# Tilt-MCU.net
KiCad netlist of a schematic drawn in Altium Designer
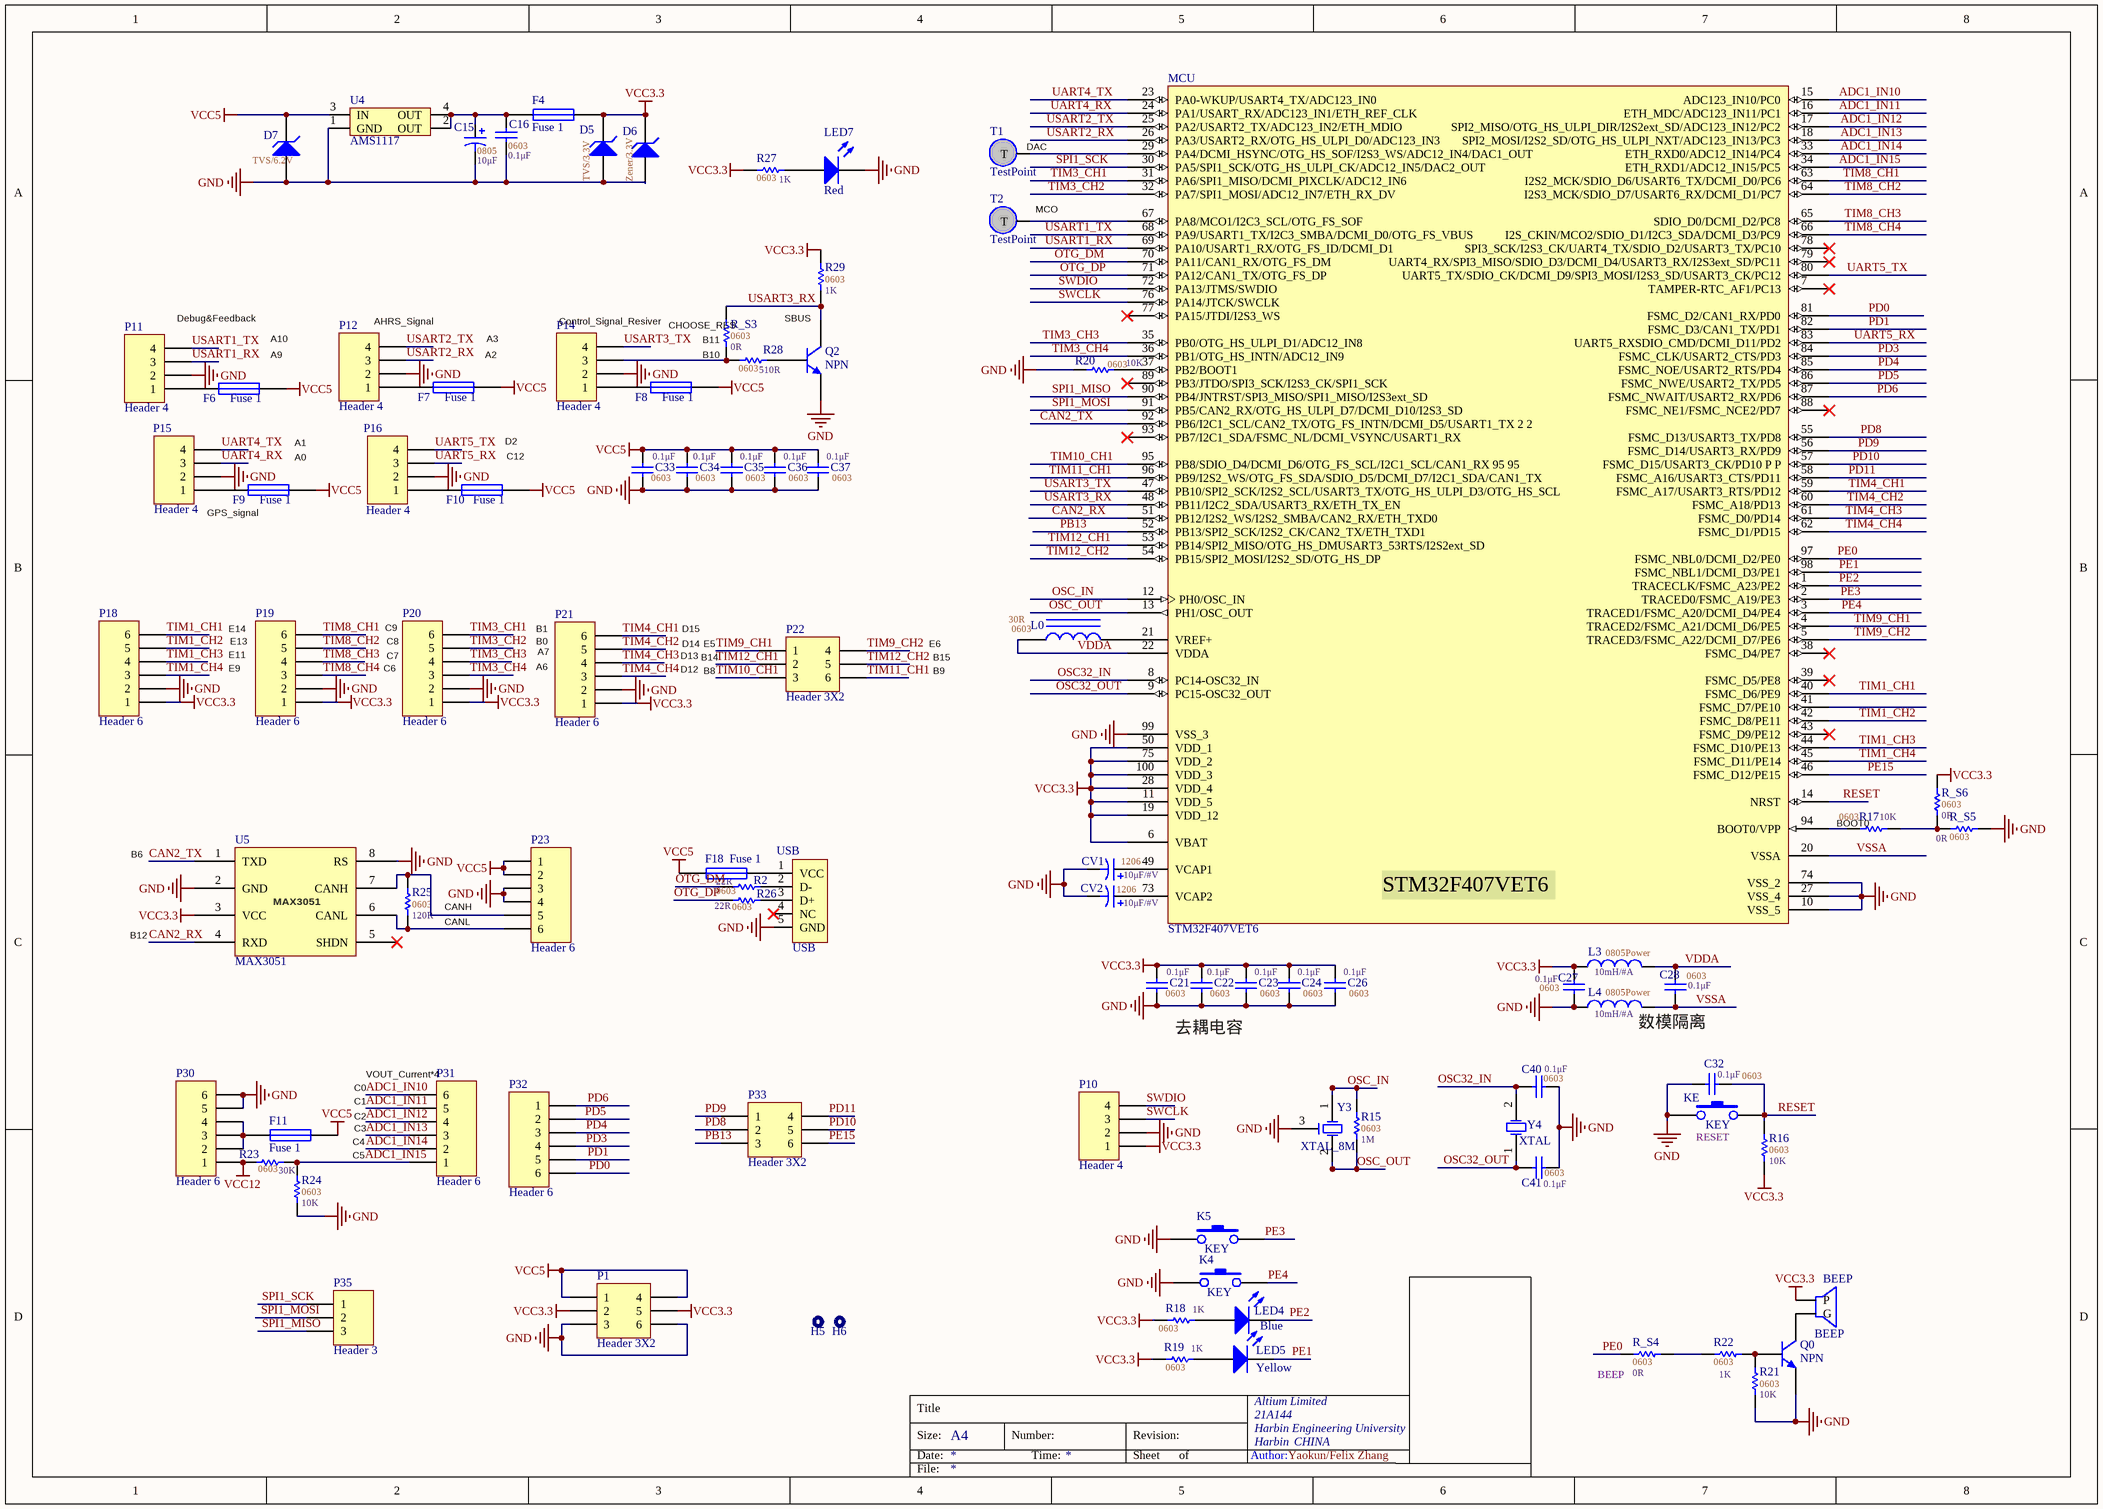
[diagram p0: Tilt-MCU.SchDoc]

(export (version "E")
  (design (tool "Eeschema 10.0.6"))
  (components
    (comp (ref "BEEP")
      (value "BEEP")
      (footprint "BELL-5")
      (libsource (lib "Belong_to_Kongkong") (part "BEEP"))
    )
    (comp (ref "C15")
      (value "10μF")
      (footprint "CAP_0805_20*12")
      (description "Polarized Capacitor (Axial)")
      (fields
        (field (name "PACKAGEREFERENCE") "0805")
        (field (name "Comment") "Polar")
        (field (name "PUBLISHER") "Altium Limited")
      )
      (libsource (lib "Belong_to_Kongkong") (part "Cap Pol"))
    )
    (comp (ref "C16")
      (value "0.1μF")
      (footprint "CAP_0603_16*08")
      (description "Capacitor")
      (fields
        (field (name "PACKAGEREFERENCE") "0603")
        (field (name "Comment") "0603")
        (field (name "PUBLISHER") "Altium Limited")
      )
      (libsource (lib "Belong_to_Kongkong") (part "Cap"))
    )
    (comp (ref "C21")
      (value "0.1μF")
      (footprint "CAP_0603_16*08")
      (description "Capacitor")
      (fields
        (field (name "PACKAGEREFERENCE") "0603")
        (field (name "Comment") "0603")
        (field (name "PUBLISHER") "Altium Limited")
      )
      (libsource (lib "Belong_to_Kongkong") (part "Cap"))
    )
    (comp (ref "C22")
      (value "0.1μF")
      (footprint "CAP_0603_16*08")
      (description "Capacitor")
      (fields
        (field (name "PACKAGEREFERENCE") "0603")
        (field (name "Comment") "0603")
        (field (name "PUBLISHER") "Altium Limited")
      )
      (libsource (lib "Belong_to_Kongkong") (part "Cap"))
    )
    (comp (ref "C23")
      (value "0.1μF")
      (footprint "CAP_0603_16*08")
      (description "Capacitor")
      (fields
        (field (name "PACKAGEREFERENCE") "0603")
        (field (name "Comment") "0603")
        (field (name "PUBLISHER") "Altium Limited")
      )
      (libsource (lib "Belong_to_Kongkong") (part "Cap"))
    )
    (comp (ref "C24")
      (value "0.1μF")
      (footprint "CAP_0603_16*08")
      (description "Capacitor")
      (fields
        (field (name "PACKAGEREFERENCE") "0603")
        (field (name "Comment") "0603")
        (field (name "PUBLISHER") "Altium Limited")
      )
      (libsource (lib "Belong_to_Kongkong") (part "Cap"))
    )
    (comp (ref "C26")
      (value "0.1μF")
      (footprint "CAP_0603_16*08")
      (description "Capacitor")
      (fields
        (field (name "PACKAGEREFERENCE") "0603")
        (field (name "Comment") "0603")
        (field (name "PUBLISHER") "Altium Limited")
      )
      (libsource (lib "Belong_to_Kongkong") (part "Cap"))
    )
    (comp (ref "C27")
      (value "0.1μF")
      (footprint "CAP_0603_16*08")
      (description "Capacitor")
      (fields
        (field (name "PACKAGEREFERENCE") "0603")
        (field (name "Comment") "0603")
        (field (name "PUBLISHER") "Altium Limited")
      )
      (libsource (lib "Belong_to_Kongkong") (part "Cap"))
    )
    (comp (ref "C28")
      (value "0.1μF")
      (footprint "CAP_0603_16*08")
      (description "Capacitor")
      (fields
        (field (name "PACKAGEREFERENCE") "0603")
        (field (name "Comment") "0603")
        (field (name "PUBLISHER") "Altium Limited")
      )
      (libsource (lib "Belong_to_Kongkong") (part "Cap"))
    )
    (comp (ref "C32")
      (value "0.1μF")
      (footprint "CAP_0603_16*08")
      (description "Capacitor")
      (fields
        (field (name "PACKAGEREFERENCE") "0603")
        (field (name "Comment") "0603")
        (field (name "PUBLISHER") "Altium Limited")
      )
      (libsource (lib "Belong_to_Kongkong") (part "Cap"))
    )
    (comp (ref "C33")
      (value "0.1μF")
      (footprint "CAP_0603_16*08")
      (description "Capacitor")
      (fields
        (field (name "PACKAGEREFERENCE") "0603")
        (field (name "Comment") "0603")
        (field (name "PUBLISHER") "Altium Limited")
      )
      (libsource (lib "Belong_to_Kongkong") (part "Cap"))
    )
    (comp (ref "C34")
      (value "0.1μF")
      (footprint "CAP_0603_16*08")
      (description "Capacitor")
      (fields
        (field (name "PACKAGEREFERENCE") "0603")
        (field (name "Comment") "0603")
        (field (name "PUBLISHER") "Altium Limited")
      )
      (libsource (lib "Belong_to_Kongkong") (part "Cap"))
    )
    (comp (ref "C35")
      (value "0.1μF")
      (footprint "CAP_0603_16*08")
      (description "Capacitor")
      (fields
        (field (name "PACKAGEREFERENCE") "0603")
        (field (name "Comment") "0603")
        (field (name "PUBLISHER") "Altium Limited")
      )
      (libsource (lib "Belong_to_Kongkong") (part "Cap"))
    )
    (comp (ref "C36")
      (value "0.1μF")
      (footprint "CAP_0603_16*08")
      (description "Capacitor")
      (fields
        (field (name "PACKAGEREFERENCE") "0603")
        (field (name "Comment") "0603")
        (field (name "PUBLISHER") "Altium Limited")
      )
      (libsource (lib "Belong_to_Kongkong") (part "Cap"))
    )
    (comp (ref "C37")
      (value "0.1μF")
      (footprint "CAP_0603_16*08")
      (description "Capacitor")
      (fields
        (field (name "PACKAGEREFERENCE") "0603")
        (field (name "Comment") "0603")
        (field (name "PUBLISHER") "Altium Limited")
      )
      (libsource (lib "Belong_to_Kongkong") (part "Cap"))
    )
    (comp (ref "C40")
      (value "0.1μF")
      (footprint "CAP_0603_16*08")
      (description "Capacitor")
      (fields
        (field (name "PACKAGEREFERENCE") "0603")
        (field (name "Comment") "0603")
        (field (name "PUBLISHER") "Altium Limited")
      )
      (libsource (lib "Belong_to_Kongkong") (part "Cap"))
    )
    (comp (ref "C41")
      (value "0.1μF")
      (footprint "CAP_0603_16*08")
      (description "Capacitor")
      (fields
        (field (name "PACKAGEREFERENCE") "0603")
        (field (name "Comment") "0603")
        (field (name "PUBLISHER") "Altium Limited")
      )
      (libsource (lib "Belong_to_Kongkong") (part "Cap"))
    )
    (comp (ref "CV1")
      (value "10μF/#V")
      (footprint "CAP_0805_20*12")
      (description "Polarized Capacitor (Axial)")
      (fields
        (field (name "PACKAGEREFERENCE") "1206")
        (field (name "Comment") "Polar")
        (field (name "PUBLISHER") "Altium Limited")
      )
      (libsource (lib "Belong_to_Kongkong") (part "Cap Pol"))
    )
    (comp (ref "CV2")
      (value "10μF/#V")
      (footprint "CAP_0805_20*12")
      (description "Polarized Capacitor (Axial)")
      (fields
        (field (name "PACKAGEREFERENCE") "1206")
        (field (name "Comment") "Polar")
        (field (name "PUBLISHER") "Altium Limited")
      )
      (libsource (lib "Belong_to_Kongkong") (part "Cap Pol"))
    )
    (comp (ref "D5")
      (value "TVS/3.3V")
      (footprint "SOD523")
      (description "Zener Diode")
      (fields (field (name "PUBLISHER") "Altium Limited"))
      (libsource (lib "Belong_to_Kongkong") (part "D Zener"))
    )
    (comp (ref "D6")
      (value "Zener/3.3V")
      (footprint "SOD323")
      (description "Zener Diode")
      (fields (field (name "PUBLISHER") "Altium Limited"))
      (libsource (lib "Belong_to_Kongkong") (part "D Zener"))
    )
    (comp (ref "D7")
      (value "TVS/6.2V")
      (footprint "SOD523")
      (description "Zener Diode")
      (fields (field (name "PUBLISHER") "Altium Limited"))
      (libsource (lib "Belong_to_Kongkong") (part "D Zener"))
    )
    (comp (ref "F4")
      (value "Fuse 1")
      (footprint "RES_0805_20*12")
      (description "Fuse")
      (fields (field (name "PUBLISHER") "Altium Limited"))
      (libsource (lib "Belong_to_Kongkong") (part "Fuse 1"))
    )
    (comp (ref "F6")
      (value "Fuse 1")
      (footprint "RES_0805_20*12")
      (description "Fuse")
      (fields (field (name "PUBLISHER") "Altium Limited"))
      (libsource (lib "Belong_to_Kongkong") (part "Fuse 1"))
    )
    (comp (ref "F7")
      (value "Fuse 1")
      (footprint "RES_0805_20*12")
      (description "Fuse")
      (fields (field (name "PUBLISHER") "Altium Limited"))
      (libsource (lib "Belong_to_Kongkong") (part "Fuse 1"))
    )
    (comp (ref "F8")
      (value "Fuse 1")
      (footprint "RES_0805_20*12")
      (description "Fuse")
      (fields (field (name "PUBLISHER") "Altium Limited"))
      (libsource (lib "Belong_to_Kongkong") (part "Fuse 1"))
    )
    (comp (ref "F9")
      (value "Fuse 1")
      (footprint "RES_0805_20*12")
      (description "Fuse")
      (fields (field (name "PUBLISHER") "Altium Limited"))
      (libsource (lib "Belong_to_Kongkong") (part "Fuse 1"))
    )
    (comp (ref "F10")
      (value "Fuse 1")
      (footprint "RES_0805_20*12")
      (description "Fuse")
      (fields (field (name "PUBLISHER") "Altium Limited"))
      (libsource (lib "Belong_to_Kongkong") (part "Fuse 1"))
    )
    (comp (ref "F11")
      (value "Fuse 1")
      (footprint "FUSE3.5*5.5")
      (description "Fuse")
      (fields (field (name "PUBLISHER") "Altium Limited"))
      (libsource (lib "Belong_to_Kongkong") (part "Fuse 1"))
    )
    (comp (ref "F18")
      (value "Fuse 1")
      (footprint "RES_0805_20*12")
      (description "Fuse")
      (fields (field (name "PUBLISHER") "Altium Limited"))
      (libsource (lib "Belong_to_Kongkong") (part "Fuse 1"))
    )
    (comp (ref "H5") (value "pad") (footprint "PAD_M2") (libsource (lib "Belong_to_Kongkong") (part "pad")))
    (comp (ref "H6") (value "pad") (footprint "PAD_M2") (libsource (lib "Belong_to_Kongkong") (part "pad")))
    (comp (ref "K4") (value "KEY") (footprint "KEY_2") (libsource (lib "Belong_to_Kongkong") (part "KEY")))
    (comp (ref "K5") (value "KEY") (footprint "KEY_2") (libsource (lib "Belong_to_Kongkong") (part "KEY")))
    (comp (ref "KE")
      (value "KEY")
      (footprint "KEY_2")
      (fields (field (name "ALTIUM_UNNAMED_1") "RESET"))
      (libsource (lib "Belong_to_Kongkong") (part "KEY"))
    )
    (comp (ref "L0")
      (value "30R")
      (footprint "IND_0603_16*08")
      (description "Magnetic-Core Inductor")
      (fields
        (field (name "PACKAGEDESCRIPTION") "0603")
        (field (name "Comment") "Inductor Iron")
        (field (name "PUBLISHER") "Altium Limited")
      )
      (libsource (lib "Belong_to_Kongkong") (part "Inductor Iron"))
    )
    (comp (ref "L3")
      (value "10mH/#A")
      (footprint "IND_0603_16*08")
      (description "Inductor")
      (fields
        (field (name "PACKAGEREFERENCE") "0805")
        (field (name "PACKAGEDESCRIPTION") "Power")
        (field (name "Comment") "MODEL?")
        (field (name "PUBLISHER") "Altium Limited")
      )
      (libsource (lib "Belong_to_Kongkong") (part "Inductor"))
    )
    (comp (ref "L4")
      (value "10mH/#A")
      (footprint "IND_0603_16*08")
      (description "Inductor")
      (fields
        (field (name "PACKAGEREFERENCE") "0805")
        (field (name "PACKAGEDESCRIPTION") "Power")
        (field (name "Comment") "MODEL?")
        (field (name "PUBLISHER") "Altium Limited")
      )
      (libsource (lib "Belong_to_Kongkong") (part "Inductor"))
    )
    (comp (ref "LED4")
      (value "Blue")
      (footprint "LED0603")
      (description "Typical RED, GREEN, YELLOW, AMBER GaAs LED")
      (fields (field (name "PUBLISHER") "Altium Limited"))
      (libsource (lib "Belong_to_Kongkong") (part "LED"))
    )
    (comp (ref "LED5")
      (value "Yellow")
      (footprint "LED0603")
      (description "Typical RED, GREEN, YELLOW, AMBER GaAs LED")
      (fields (field (name "PUBLISHER") "Altium Limited"))
      (libsource (lib "Belong_to_Kongkong") (part "LED"))
    )
    (comp (ref "LED7")
      (value "Red")
      (footprint "LED0603")
      (description "Typical RED, GREEN, YELLOW, AMBER GaAs LED")
      (fields (field (name "PUBLISHER") "Altium Limited"))
      (libsource (lib "Belong_to_Kongkong") (part "LED"))
    )
    (comp (ref "MCU")
      (value "STM32F407VET6")
      (footprint "LQFP100_1")
      (libsource (lib "Belong_to_Kongkong") (part "STM32F407VET6"))
    )
    (comp (ref "P1")
      (value "Header 3X2")
      (footprint "HEADER2*3_PIN")
      (description "Header, 3-Pin, Dual row")
      (fields (field (name "PUBLISHER") "Altium Limited"))
      (libsource (lib "Belong_to_Kongkong") (part "Header 3X2"))
    )
    (comp (ref "P10")
      (value "Header 4")
      (footprint "Modolex_4P")
      (description "Header, 4-Pin")
      (fields (field (name "PUBLISHER") "Altium Limited"))
      (libsource (lib "Belong_to_Kongkong") (part "Header 4"))
    )
    (comp (ref "P11")
      (value "Header 4")
      (footprint "Modolex_4P")
      (description "Header, 4-Pin")
      (fields (field (name "PUBLISHER") "Altium Limited"))
      (libsource (lib "Belong_to_Kongkong") (part "Header 4"))
    )
    (comp (ref "P12")
      (value "Header 4")
      (footprint "Modolex_4P")
      (description "Header, 4-Pin")
      (fields (field (name "PUBLISHER") "Altium Limited"))
      (libsource (lib "Belong_to_Kongkong") (part "Header 4"))
    )
    (comp (ref "P14")
      (value "Header 4")
      (footprint "Modolex_4P")
      (description "Header, 4-Pin")
      (fields (field (name "PUBLISHER") "Altium Limited"))
      (libsource (lib "Belong_to_Kongkong") (part "Header 4"))
    )
    (comp (ref "P15")
      (value "Header 4")
      (footprint "Modolex_4P")
      (description "Header, 4-Pin")
      (fields (field (name "PUBLISHER") "Altium Limited"))
      (libsource (lib "Belong_to_Kongkong") (part "Header 4"))
    )
    (comp (ref "P16")
      (value "Header 4")
      (footprint "Modolex_4P")
      (description "Header, 4-Pin")
      (fields (field (name "PUBLISHER") "Altium Limited"))
      (libsource (lib "Belong_to_Kongkong") (part "Header 4"))
    )
    (comp (ref "P18")
      (value "Header 6")
      (footprint "Modolex_6P")
      (description "Header, 6-Pin")
      (fields (field (name "PUBLISHER") "Altium Limited"))
      (libsource (lib "Belong_to_Kongkong") (part "Header 6"))
    )
    (comp (ref "P19")
      (value "Header 6")
      (footprint "Modolex_6P")
      (description "Header, 6-Pin")
      (fields (field (name "PUBLISHER") "Altium Limited"))
      (libsource (lib "Belong_to_Kongkong") (part "Header 6"))
    )
    (comp (ref "P20")
      (value "Header 6")
      (footprint "Modolex_6P")
      (description "Header, 6-Pin")
      (fields (field (name "PUBLISHER") "Altium Limited"))
      (libsource (lib "Belong_to_Kongkong") (part "Header 6"))
    )
    (comp (ref "P21")
      (value "Header 6")
      (footprint "Modolex_6P")
      (description "Header, 6-Pin")
      (fields (field (name "PUBLISHER") "Altium Limited"))
      (libsource (lib "Belong_to_Kongkong") (part "Header 6"))
    )
    (comp (ref "P22")
      (value "Header 3X2")
      (footprint "HEADER2*3_PIN")
      (description "Header, 3-Pin, Dual row")
      (fields (field (name "PUBLISHER") "Altium Limited"))
      (libsource (lib "Belong_to_Kongkong") (part "Header 3X2"))
    )
    (comp (ref "P23")
      (value "Header 6")
      (footprint "Modolex_6P")
      (description "Header, 6-Pin")
      (fields (field (name "PUBLISHER") "Altium Limited"))
      (libsource (lib "") (part "Header 6_1"))
    )
    (comp (ref "P30")
      (value "Header 6")
      (footprint "Modolex_6P")
      (description "Header, 6-Pin")
      (fields (field (name "PUBLISHER") "Altium Limited"))
      (libsource (lib "Belong_to_Kongkong") (part "Header 6"))
    )
    (comp (ref "P31")
      (value "Header 6")
      (footprint "Modolex_6P")
      (description "Header, 6-Pin")
      (fields (field (name "PUBLISHER") "Altium Limited"))
      (libsource (lib "") (part "Header 6_2"))
    )
    (comp (ref "P32")
      (value "Header 6")
      (footprint "Modolex_6P")
      (description "Header, 6-Pin")
      (fields (field (name "PUBLISHER") "Altium Limited"))
      (libsource (lib "") (part "Header 6_3"))
    )
    (comp (ref "P33")
      (value "Header 3X2")
      (footprint "HEADER2*3_PIN")
      (description "Header, 3-Pin, Dual row")
      (fields (field (name "PUBLISHER") "Altium Limited"))
      (libsource (lib "Belong_to_Kongkong") (part "Header 3X2"))
    )
    (comp (ref "P35")
      (value "Header 3")
      (footprint "HEADER1*3_PIN")
      (description "Header, 3-Pin")
      (fields (field (name "PUBLISHER") "Altium Limited"))
      (libsource (lib "Belong_to_Kongkong") (part "Header 3"))
    )
    (comp (ref "Q0")
      (value "NPN")
      (footprint "SOT23_J3Y")
      (description "NPN Bipolar Transistor")
      (fields (field (name "PUBLISHER") "Altium Limited"))
      (libsource (lib "Belong_to_Kongkong") (part "NPN"))
    )
    (comp (ref "Q2")
      (value "NPN")
      (footprint "SOT23_J3Y")
      (description "NPN Bipolar Transistor")
      (fields (field (name "PUBLISHER") "Altium Limited"))
      (libsource (lib "Belong_to_Kongkong") (part "NPN"))
    )
    (comp (ref "R2")
      (value "22R")
      (footprint "RES_0603_16*08")
      (description "Resistor")
      (fields
        (field (name "PACKAGEREFERENCE") "0603")
        (field (name "Comment") "SMD")
        (field (name "PUBLISHER") "Altium Limited")
      )
      (libsource (lib "Belong_to_Kongkong") (part "RES_SMD"))
    )
    (comp (ref "R15")
      (value "1M")
      (footprint "RES_0805_20*12")
      (description "Resistor")
      (fields
        (field (name "PACKAGEREFERENCE") "0603")
        (field (name "Comment") "SMD")
        (field (name "PUBLISHER") "Altium Limited")
      )
      (libsource (lib "Belong_to_Kongkong") (part "RES_SMD"))
    )
    (comp (ref "R16")
      (value "10K")
      (footprint "RES_0603_16*08")
      (description "Resistor")
      (fields
        (field (name "PACKAGEREFERENCE") "0603")
        (field (name "Comment") "SMD")
        (field (name "PUBLISHER") "Altium Limited")
      )
      (libsource (lib "Belong_to_Kongkong") (part "RES_SMD"))
    )
    (comp (ref "R17")
      (value "10K")
      (footprint "RES_0603_16*08")
      (description "Resistor")
      (fields
        (field (name "PACKAGEREFERENCE") "0603")
        (field (name "Comment") "SMD")
        (field (name "PUBLISHER") "Altium Limited")
      )
      (libsource (lib "Belong_to_Kongkong") (part "RES_SMD"))
    )
    (comp (ref "R18")
      (value "1K")
      (footprint "RES_0603_16*08")
      (description "Resistor")
      (fields
        (field (name "PACKAGEREFERENCE") "0603")
        (field (name "Comment") "SMD")
        (field (name "PUBLISHER") "Altium Limited")
      )
      (libsource (lib "Belong_to_Kongkong") (part "RES_SMD"))
    )
    (comp (ref "R19")
      (value "1K")
      (footprint "RES_0603_16*08")
      (description "Resistor")
      (fields
        (field (name "PACKAGEREFERENCE") "0603")
        (field (name "Comment") "SMD")
        (field (name "PUBLISHER") "Altium Limited")
      )
      (libsource (lib "Belong_to_Kongkong") (part "RES_SMD"))
    )
    (comp (ref "R20")
      (value "10K")
      (footprint "RES_0603_16*08")
      (description "Resistor")
      (fields
        (field (name "PACKAGEREFERENCE") "0603")
        (field (name "Comment") "SMD")
        (field (name "PUBLISHER") "Altium Limited")
      )
      (libsource (lib "Belong_to_Kongkong") (part "RES_SMD"))
    )
    (comp (ref "R21")
      (value "10K")
      (footprint "RES_0603_16*08")
      (description "Resistor")
      (fields
        (field (name "PACKAGEREFERENCE") "0603")
        (field (name "Comment") "SMD")
        (field (name "PUBLISHER") "Altium Limited")
      )
      (libsource (lib "Belong_to_Kongkong") (part "RES_SMD"))
    )
    (comp (ref "R22")
      (value "1K")
      (footprint "RES_0603_16*08")
      (description "Resistor")
      (fields
        (field (name "PACKAGEREFERENCE") "0603")
        (field (name "Comment") "SMD")
        (field (name "PUBLISHER") "Altium Limited")
      )
      (libsource (lib "Belong_to_Kongkong") (part "RES_SMD"))
    )
    (comp (ref "R23")
      (value "30K")
      (footprint "RES_0805_20*12")
      (description "Resistor")
      (fields
        (field (name "PACKAGEREFERENCE") "0603")
        (field (name "Comment") "SMD")
        (field (name "PUBLISHER") "Altium Limited")
      )
      (libsource (lib "Belong_to_Kongkong") (part "RES_SMD"))
    )
    (comp (ref "R24")
      (value "10K")
      (footprint "RES_0805_20*12")
      (description "Resistor")
      (fields
        (field (name "PACKAGEREFERENCE") "0603")
        (field (name "Comment") "SMD")
        (field (name "PUBLISHER") "Altium Limited")
      )
      (libsource (lib "Belong_to_Kongkong") (part "RES_SMD"))
    )
    (comp (ref "R25")
      (value "120R")
      (footprint "RES_0805_20*12")
      (description "Resistor")
      (fields
        (field (name "PACKAGEREFERENCE") "0603")
        (field (name "Comment") "SMD")
        (field (name "PUBLISHER") "Altium Limited")
      )
      (libsource (lib "Belong_to_Kongkong") (part "RES_SMD"))
    )
    (comp (ref "R26")
      (value "22R")
      (footprint "RES_0603_16*08")
      (description "Resistor")
      (fields
        (field (name "PACKAGEREFERENCE") "0603")
        (field (name "Comment") "SMD")
        (field (name "PUBLISHER") "Altium Limited")
      )
      (libsource (lib "Belong_to_Kongkong") (part "RES_SMD"))
    )
    (comp (ref "R27")
      (value "1K")
      (footprint "RES_0603_16*08")
      (description "Resistor")
      (fields
        (field (name "PACKAGEREFERENCE") "0603")
        (field (name "Comment") "SMD")
        (field (name "PUBLISHER") "Altium Limited")
      )
      (libsource (lib "Belong_to_Kongkong") (part "RES_SMD"))
    )
    (comp (ref "R28")
      (value "510R")
      (footprint "RES_0603_16*08")
      (description "Resistor")
      (fields
        (field (name "PACKAGEREFERENCE") "0603")
        (field (name "Comment") "SMD")
        (field (name "PUBLISHER") "Altium Limited")
      )
      (libsource (lib "Belong_to_Kongkong") (part "RES_SMD"))
    )
    (comp (ref "R29")
      (value "1K")
      (footprint "RES_0603_16*08")
      (description "Resistor")
      (fields
        (field (name "PACKAGEREFERENCE") "0603")
        (field (name "Comment") "SMD")
        (field (name "PUBLISHER") "Altium Limited")
      )
      (libsource (lib "Belong_to_Kongkong") (part "RES_SMD"))
    )
    (comp (ref "R_S3")
      (value "0R")
      (footprint "RES_0402_10*06")
      (description "Resistor")
      (fields
        (field (name "PACKAGEREFERENCE") "0603")
        (field (name "Comment") "SMD")
        (field (name "PUBLISHER") "Altium Limited")
      )
      (libsource (lib "Belong_to_Kongkong") (part "RES_SMD"))
    )
    (comp (ref "R_S4")
      (value "0R")
      (footprint "RES_0402_10*06")
      (description "Resistor")
      (fields
        (field (name "PACKAGEREFERENCE") "0603")
        (field (name "Comment") "SMD")
        (field (name "PUBLISHER") "Altium Limited")
      )
      (libsource (lib "Belong_to_Kongkong") (part "RES_SMD"))
    )
    (comp (ref "R_S5")
      (value "0R")
      (footprint "RES_0402_10*06")
      (description "Resistor")
      (fields
        (field (name "PACKAGEREFERENCE") "0603")
        (field (name "Comment") "SMD")
        (field (name "PUBLISHER") "Altium Limited")
      )
      (libsource (lib "Belong_to_Kongkong") (part "RES_SMD"))
    )
    (comp (ref "R_S6")
      (value "0R")
      (footprint "RES_0402_10*06")
      (description "Resistor")
      (fields
        (field (name "PACKAGEREFERENCE") "0603")
        (field (name "Comment") "SMD")
        (field (name "PUBLISHER") "Altium Limited")
      )
      (libsource (lib "Belong_to_Kongkong") (part "RES_SMD"))
    )
    (comp (ref "T1")
      (value "TestPoint")
      (footprint "TestPoint")
      (libsource (lib "Belong_to_Kongkong") (part "TestPoint"))
    )
    (comp (ref "T2")
      (value "TestPoint")
      (footprint "TestPoint")
      (libsource (lib "Belong_to_Kongkong") (part "TestPoint"))
    )
    (comp (ref "U4")
      (value "AMS1117")
      (footprint "SOT223_M")
      (libsource (lib "Belong_to_Kongkong") (part "AMS1117"))
    )
    (comp (ref "U5") (value "MAX3051") (footprint "SO8_M") (libsource (lib "my_lib") (part "MAX3051")))
    (comp (ref "USB")
      (value "USB")
      (footprint "USB_micro_S")
      (libsource (lib "Belong_to_Kongkong") (part "USB5"))
    )
    (comp (ref "Y3")
      (value "XTAL_8M")
      (footprint "XTAL_SMD_8M")
      (libsource (lib "Belong_to_Kongkong") (part "XTAL_8M"))
    )
    (comp (ref "Y4")
      (value "XTAL")
      (footprint "XTAL32")
      (description "Crystal Oscillator")
      (fields (field (name "PUBLISHER") "Altium Limited"))
      (libsource (lib "Belong_to_Kongkong") (part "XTAL"))
    )
  )
  (nets
    (net (code "1") (name "/ADC1_IN10") (class "Default")
      (node (ref "MCU") (pin "15") (pinfunction "ADC123_IN10/PC0_15") (pintype "bidirectional"))
      (node (ref "P31") (pin "6") (pinfunction "6_6") (pintype "passive"))
    )
    (net (code "2") (name "/ADC1_IN11") (class "Default")
      (node (ref "MCU") (pin "16") (pinfunction "ETH_MDC/ADC123_IN11/PC1_16") (pintype "bidirectional"))
      (node (ref "P31") (pin "5") (pinfunction "5_5") (pintype "passive"))
    )
    (net (code "3") (name "/ADC1_IN12") (class "Default")
      (node (ref "MCU") (pin "17") (pinfunction "SPI2_MISO/OTG_HS_ULPI_DIR/I2S2ext_SD/ADC123_IN12/PC2_17") (pintype "bidirectional"))
      (node (ref "P31") (pin "4") (pinfunction "4_4") (pintype "passive"))
    )
    (net (code "4") (name "/ADC1_IN13") (class "Default")
      (node (ref "MCU") (pin "18") (pinfunction "SPI2_MOSI/I2S2_SD/OTG_HS_ULPI_NXT/ADC123_IN13/PC3_18") (pintype "bidirectional"))
      (node (ref "P31") (pin "3") (pinfunction "3_3") (pintype "passive"))
    )
    (net (code "5") (name "/ADC1_IN14") (class "Default")
      (node (ref "MCU") (pin "33") (pinfunction "ETH_RXD0/ADC12_IN14/PC4_33") (pintype "bidirectional"))
      (node (ref "P31") (pin "2") (pinfunction "2_2") (pintype "passive"))
    )
    (net (code "6") (name "/ADC1_IN15") (class "Default")
      (node (ref "MCU") (pin "34") (pinfunction "ETH_RXD1/ADC12_IN15/PC5_34") (pintype "bidirectional"))
      (node (ref "P31") (pin "1") (pinfunction "1_1") (pintype "passive"))
      (node (ref "R23") (pin "2") (pinfunction "2_2") (pintype "passive"))
      (node (ref "R24") (pin "2") (pinfunction "2_2") (pintype "passive"))
    )
    (net (code "7") (name "/CAN2_RX") (class "Default")
      (node (ref "MCU") (pin "51") (pinfunction "PB12/I2S2_WS/I2S2_SMBA/CAN2_RX/ETH_TXD0_51") (pintype "bidirectional"))
      (node (ref "U5") (pin "4") (pinfunction "RXD_4") (pintype "passive"))
    )
    (net (code "8") (name "/CAN2_TX") (class "Default")
      (node (ref "MCU") (pin "92") (pinfunction "PB6/I2C1_SCL/CAN2_TX/OTG_FS_INTN/DCMI_D5/USART1_TX_2_2_92") (pintype "bidirectional"))
      (node (ref "U5") (pin "1") (pinfunction "TXD_1") (pintype "passive"))
    )
    (net (code "9") (name "/OSC32_IN") (class "Default")
      (node (ref "C40") (pin "1") (pinfunction "1_1") (pintype "passive"))
      (node (ref "MCU") (pin "8") (pinfunction "PC14-OSC32_IN_8") (pintype "bidirectional"))
      (node (ref "Y4") (pin "2") (pinfunction "OSC2_2") (pintype "passive"))
    )
    (net (code "10") (name "/OSC32_OUT") (class "Default")
      (node (ref "C41") (pin "1") (pinfunction "1_1") (pintype "passive"))
      (node (ref "MCU") (pin "9") (pinfunction "PC15-OSC32_OUT_9") (pintype "bidirectional"))
      (node (ref "Y4") (pin "1") (pinfunction "OSC1_1") (pintype "passive"))
    )
    (net (code "11") (name "/OSC_IN") (class "Default")
      (node (ref "MCU") (pin "12") (pinfunction "PH0/OSC_IN_12") (pintype "input"))
      (node (ref "R15") (pin "2") (pinfunction "2_2") (pintype "passive"))
      (node (ref "Y3") (pin "1") (pinfunction "OSC1_1") (pintype "passive"))
    )
    (net (code "12") (name "/OSC_OUT") (class "Default")
      (node (ref "MCU") (pin "13") (pinfunction "PH1/OSC_OUT_13") (pintype "output"))
      (node (ref "R15") (pin "1") (pinfunction "1_1") (pintype "passive"))
      (node (ref "Y3") (pin "2") (pinfunction "OSC2_2") (pintype "passive"))
    )
    (net (code "13") (name "/OTG_DM") (class "Default")
      (node (ref "MCU") (pin "70") (pinfunction "PA11/CAN1_RX/OTG_FS_DM_70") (pintype "bidirectional"))
      (node (ref "R2") (pin "1") (pinfunction "1_1") (pintype "passive"))
    )
    (net (code "14") (name "/OTG_DP") (class "Default")
      (node (ref "MCU") (pin "71") (pinfunction "PA12/CAN1_TX/OTG_FS_DP_71") (pintype "bidirectional"))
      (node (ref "R26") (pin "1") (pinfunction "1_1") (pintype "passive"))
    )
    (net (code "15") (name "/PB13") (class "Default")
      (node (ref "MCU") (pin "52") (pinfunction "PB13/SPI2_SCK/I2S2_CK/CAN2_TX/ETH_TXD1_52") (pintype "bidirectional"))
      (node (ref "P33") (pin "3") (pinfunction "3_3") (pintype "passive"))
    )
    (net (code "16") (name "/PD0") (class "Default")
      (node (ref "MCU") (pin "81") (pinfunction "FSMC_D2/CAN1_RX/PD0_81") (pintype "bidirectional"))
      (node (ref "P32") (pin "6") (pinfunction "6_6") (pintype "passive"))
    )
    (net (code "17") (name "/PD1") (class "Default")
      (node (ref "MCU") (pin "82") (pinfunction "FSMC_D3/CAN1_TX/PD1_82") (pintype "bidirectional"))
      (node (ref "P32") (pin "5") (pinfunction "5_5") (pintype "passive"))
    )
    (net (code "18") (name "/PD3") (class "Default")
      (node (ref "MCU") (pin "84") (pinfunction "FSMC_CLK/USART2_CTS/PD3_84") (pintype "bidirectional"))
      (node (ref "P32") (pin "4") (pinfunction "4_4") (pintype "passive"))
    )
    (net (code "19") (name "/PD4") (class "Default")
      (node (ref "MCU") (pin "85") (pinfunction "FSMC_NOE/USART2_RTS/PD4_85") (pintype "bidirectional"))
      (node (ref "P32") (pin "3") (pinfunction "3_3") (pintype "passive"))
    )
    (net (code "20") (name "/PD5") (class "Default")
      (node (ref "MCU") (pin "86") (pinfunction "FSMC_NWE/USART2_TX/PD5_86") (pintype "bidirectional"))
      (node (ref "P32") (pin "2") (pinfunction "2_2") (pintype "passive"))
    )
    (net (code "21") (name "/PD6") (class "Default")
      (node (ref "MCU") (pin "87") (pinfunction "FSMC_NWAIT/USART2_RX/PD6_87") (pintype "bidirectional"))
      (node (ref "P32") (pin "1") (pinfunction "1_1") (pintype "passive"))
    )
    (net (code "22") (name "/PD8") (class "Default")
      (node (ref "MCU") (pin "55") (pinfunction "FSMC_D13/USART3_TX/PD8_55") (pintype "bidirectional"))
      (node (ref "P33") (pin "2") (pinfunction "2_2") (pintype "passive"))
    )
    (net (code "23") (name "/PD9") (class "Default")
      (node (ref "MCU") (pin "56") (pinfunction "FSMC_D14/USART3_RX/PD9_56") (pintype "bidirectional"))
      (node (ref "P33") (pin "1") (pinfunction "1_1") (pintype "passive"))
    )
    (net (code "24") (name "/PD10") (class "Default")
      (node (ref "MCU") (pin "57") (pinfunction "FSMC_D15/USART3_CK/PD10_P_P_57") (pintype "bidirectional"))
      (node (ref "P33") (pin "5") (pinfunction "5_5") (pintype "passive"))
    )
    (net (code "25") (name "/PD11") (class "Default")
      (node (ref "MCU") (pin "58") (pinfunction "FSMC_A16/USART3_CTS/PD11_58") (pintype "bidirectional"))
      (node (ref "P33") (pin "4") (pinfunction "4_4") (pintype "passive"))
    )
    (net (code "26") (name "/PE0") (class "Default")
      (node (ref "MCU") (pin "97") (pinfunction "FSMC_NBL0/DCMI_D2/PE0_97") (pintype "bidirectional"))
      (node (ref "R_S4") (pin "2") (pinfunction "2_2") (pintype "passive"))
    )
    (net (code "27") (name "/PE1") (class "Default")
      (node (ref "LED5") (pin "2") (pinfunction "K_2") (pintype "passive"))
      (node (ref "MCU") (pin "98") (pinfunction "FSMC_NBL1/DCMI_D3/PE1_98") (pintype "bidirectional"))
    )
    (net (code "28") (name "/PE2") (class "Default")
      (node (ref "LED4") (pin "2") (pinfunction "K_2") (pintype "passive"))
      (node (ref "MCU") (pin "1") (pinfunction "TRACECLK/FSMC_A23/PE2_1") (pintype "bidirectional"))
    )
    (net (code "29") (name "/PE3") (class "Default")
      (node (ref "K5") (pin "2") (pinfunction "2_2") (pintype "passive"))
      (node (ref "MCU") (pin "2") (pinfunction "TRACED0/FSMC_A19/PE3_2") (pintype "bidirectional"))
    )
    (net (code "30") (name "/PE4") (class "Default")
      (node (ref "K4") (pin "2") (pinfunction "2_2") (pintype "passive"))
      (node (ref "MCU") (pin "3") (pinfunction "TRACED1/FSMC_A20/DCMI_D4/PE4_3") (pintype "bidirectional"))
    )
    (net (code "31") (name "/PE15") (class "Default")
      (node (ref "MCU") (pin "46") (pinfunction "FSMC_D12/PE15_46") (pintype "bidirectional"))
      (node (ref "P33") (pin "6") (pinfunction "6_6") (pintype "passive"))
    )
    (net (code "32") (name "/RESET") (class "Default")
      (node (ref "C32") (pin "2") (pinfunction "2_2") (pintype "passive"))
      (node (ref "KE") (pin "2") (pinfunction "2_2") (pintype "passive"))
      (node (ref "MCU") (pin "14") (pinfunction "NRST_14") (pintype "bidirectional"))
      (node (ref "R16") (pin "2") (pinfunction "2_2") (pintype "passive"))
    )
    (net (code "33") (name "/SPI1_MISO") (class "Default")
      (node (ref "MCU") (pin "90") (pinfunction "PB4/JNTRST/SPI3_MISO/SPI1_MISO/I2S3ext_SD_90") (pintype "bidirectional"))
      (node (ref "P35") (pin "3") (pinfunction "3_3") (pintype "passive"))
    )
    (net (code "34") (name "/SPI1_MOSI") (class "Default")
      (node (ref "MCU") (pin "91") (pinfunction "PB5/CAN2_RX/OTG_HS_ULPI_D7/DCMI_D10/I2S3_SD_91") (pintype "bidirectional"))
      (node (ref "P35") (pin "2") (pinfunction "2_2") (pintype "passive"))
    )
    (net (code "35") (name "/SPI1_SCK") (class "Default")
      (node (ref "MCU") (pin "30") (pinfunction "PA5/SPI1_SCK/OTG_HS_ULPI_CK/ADC12_IN5/DAC2_OUT_30") (pintype "bidirectional"))
      (node (ref "P35") (pin "1") (pinfunction "1_1") (pintype "passive"))
    )
    (net (code "36") (name "/SWCLK") (class "Default")
      (node (ref "MCU") (pin "76") (pinfunction "PA14/JTCK/SWCLK_76") (pintype "bidirectional"))
      (node (ref "P10") (pin "3") (pinfunction "3_3") (pintype "passive"))
    )
    (net (code "37") (name "/SWDIO") (class "Default")
      (node (ref "MCU") (pin "72") (pinfunction "PA13/JTMS/SWDIO_72") (pintype "bidirectional"))
      (node (ref "P10") (pin "4") (pinfunction "4_4") (pintype "passive"))
    )
    (net (code "38") (name "/TIM1_CH1") (class "Default")
      (node (ref "MCU") (pin "40") (pinfunction "FSMC_D6/PE9_40") (pintype "bidirectional"))
      (node (ref "P18") (pin "6") (pinfunction "6_6") (pintype "passive"))
    )
    (net (code "39") (name "/TIM1_CH2") (class "Default")
      (node (ref "MCU") (pin "42") (pinfunction "FSMC_D8/PE11_42") (pintype "bidirectional"))
      (node (ref "P18") (pin "5") (pinfunction "5_5") (pintype "passive"))
    )
    (net (code "40") (name "/TIM1_CH3") (class "Default")
      (node (ref "MCU") (pin "44") (pinfunction "FSMC_D10/PE13_44") (pintype "bidirectional"))
      (node (ref "P18") (pin "4") (pinfunction "4_4") (pintype "passive"))
    )
    (net (code "41") (name "/TIM1_CH4") (class "Default")
      (node (ref "MCU") (pin "45") (pinfunction "FSMC_D11/PE14_45") (pintype "bidirectional"))
      (node (ref "P18") (pin "3") (pinfunction "3_3") (pintype "passive"))
    )
    (net (code "42") (name "/TIM3_CH1") (class "Default")
      (node (ref "MCU") (pin "31") (pinfunction "PA6/SPI1_MISO/DCMI_PIXCLK/ADC12_IN6_31") (pintype "bidirectional"))
      (node (ref "P20") (pin "6") (pinfunction "6_6") (pintype "passive"))
    )
    (net (code "43") (name "/TIM3_CH2") (class "Default")
      (node (ref "MCU") (pin "32") (pinfunction "PA7/SPI1_MOSI/ADC12_IN7/ETH_RX_DV_32") (pintype "bidirectional"))
      (node (ref "P20") (pin "5") (pinfunction "5_5") (pintype "passive"))
    )
    (net (code "44") (name "/TIM3_CH3") (class "Default")
      (node (ref "MCU") (pin "35") (pinfunction "PB0/OTG_HS_ULPI_D1/ADC12_IN8_35") (pintype "bidirectional"))
      (node (ref "P20") (pin "4") (pinfunction "4_4") (pintype "passive"))
    )
    (net (code "45") (name "/TIM3_CH4") (class "Default")
      (node (ref "MCU") (pin "36") (pinfunction "PB1/OTG_HS_INTN/ADC12_IN9_36") (pintype "bidirectional"))
      (node (ref "P20") (pin "3") (pinfunction "3_3") (pintype "passive"))
    )
    (net (code "46") (name "/TIM4_CH1") (class "Default")
      (node (ref "MCU") (pin "59") (pinfunction "FSMC_A17/USART3_RTS/PD12_59") (pintype "bidirectional"))
      (node (ref "P21") (pin "6") (pinfunction "6_6") (pintype "passive"))
    )
    (net (code "47") (name "/TIM4_CH2") (class "Default")
      (node (ref "MCU") (pin "60") (pinfunction "FSMC_A18/PD13_60") (pintype "bidirectional"))
      (node (ref "P21") (pin "5") (pinfunction "5_5") (pintype "passive"))
    )
    (net (code "48") (name "/TIM4_CH3") (class "Default")
      (node (ref "MCU") (pin "61") (pinfunction "FSMC_D0/PD14_61") (pintype "bidirectional"))
      (node (ref "P21") (pin "4") (pinfunction "4_4") (pintype "passive"))
    )
    (net (code "49") (name "/TIM4_CH4") (class "Default")
      (node (ref "MCU") (pin "62") (pinfunction "FSMC_D1/PD15_62") (pintype "bidirectional"))
      (node (ref "P21") (pin "3") (pinfunction "3_3") (pintype "passive"))
    )
    (net (code "50") (name "/TIM8_CH1") (class "Default")
      (node (ref "MCU") (pin "63") (pinfunction "I2S2_MCK/SDIO_D6/USART6_TX/DCMI_D0/PC6_63") (pintype "bidirectional"))
      (node (ref "P19") (pin "6") (pinfunction "6_6") (pintype "passive"))
    )
    (net (code "51") (name "/TIM8_CH2") (class "Default")
      (node (ref "MCU") (pin "64") (pinfunction "I2S3_MCK/SDIO_D7/USART6_RX/DCMI_D1/PC7_64") (pintype "bidirectional"))
      (node (ref "P19") (pin "5") (pinfunction "5_5") (pintype "passive"))
    )
    (net (code "52") (name "/TIM8_CH3") (class "Default")
      (node (ref "MCU") (pin "65") (pinfunction "SDIO_D0/DCMI_D2/PC8_65") (pintype "bidirectional"))
      (node (ref "P19") (pin "4") (pinfunction "4_4") (pintype "passive"))
    )
    (net (code "53") (name "/TIM8_CH4") (class "Default")
      (node (ref "MCU") (pin "66") (pinfunction "I2S_CKIN/MCO2/SDIO_D1/I2C3_SDA/DCMI_D3/PC9_66") (pintype "bidirectional"))
      (node (ref "P19") (pin "3") (pinfunction "3_3") (pintype "passive"))
    )
    (net (code "54") (name "/TIM9_CH1") (class "Default")
      (node (ref "MCU") (pin "4") (pinfunction "TRACED2/FSMC_A21/DCMI_D6/PE5_4") (pintype "bidirectional"))
      (node (ref "P22") (pin "1") (pinfunction "1_1") (pintype "passive"))
    )
    (net (code "55") (name "/TIM9_CH2") (class "Default")
      (node (ref "MCU") (pin "5") (pinfunction "TRACED3/FSMC_A22/DCMI_D7/PE6_5") (pintype "bidirectional"))
      (node (ref "P22") (pin "4") (pinfunction "4_4") (pintype "passive"))
    )
    (net (code "56") (name "/TIM10_CH1") (class "Default")
      (node (ref "MCU") (pin "95") (pinfunction "PB8/SDIO_D4/DCMI_D6/OTG_FS_SCL/I2C1_SCL/CAN1_RX_95_95_95") (pintype "bidirectional"))
      (node (ref "P22") (pin "3") (pinfunction "3_3") (pintype "passive"))
    )
    (net (code "57") (name "/TIM11_CH1") (class "Default")
      (node (ref "MCU") (pin "96") (pinfunction "PB9/I2S2_WS/OTG_FS_SDA/SDIO_D5/DCMI_D7/I2C1_SDA/CAN1_TX_96") (pintype "bidirectional"))
      (node (ref "P22") (pin "6") (pinfunction "6_6") (pintype "passive"))
    )
    (net (code "58") (name "/TIM12_CH1") (class "Default")
      (node (ref "MCU") (pin "53") (pinfunction "PB14/SPI2_MISO/OTG_HS_DMUSART3_53RTS/I2S2ext_SD_53") (pintype "bidirectional"))
      (node (ref "P22") (pin "2") (pinfunction "2_2") (pintype "passive"))
    )
    (net (code "59") (name "/TIM12_CH2") (class "Default")
      (node (ref "MCU") (pin "54") (pinfunction "PB15/SPI2_MOSI/I2S2_SD/OTG_HS_DP_54") (pintype "bidirectional"))
      (node (ref "P22") (pin "5") (pinfunction "5_5") (pintype "passive"))
    )
    (net (code "60") (name "/UART4_RX") (class "Default")
      (node (ref "MCU") (pin "24") (pinfunction "PA1/USART_RX/ADC123_IN1/ETH_REF_CLK_24") (pintype "bidirectional"))
      (node (ref "P15") (pin "3") (pinfunction "3_3") (pintype "passive"))
    )
    (net (code "61") (name "/UART4_TX") (class "Default")
      (node (ref "MCU") (pin "23") (pinfunction "PA0-WKUP/USART4_TX/ADC123_IN0_23") (pintype "bidirectional"))
      (node (ref "P15") (pin "4") (pinfunction "4_4") (pintype "passive"))
    )
    (net (code "62") (name "/UART5_RX") (class "Default")
      (node (ref "MCU") (pin "83") (pinfunction "UART5_RXSDIO_CMD/DCMI_D11/PD2_83") (pintype "bidirectional"))
      (node (ref "P16") (pin "3") (pinfunction "3_3") (pintype "passive"))
    )
    (net (code "63") (name "/UART5_TX") (class "Default")
      (node (ref "MCU") (pin "80") (pinfunction "UART5_TX/SDIO_CK/DCMI_D9/SPI3_MOSI/I2S3_SD/USART3_CK/PC12_80") (pintype "bidirectional"))
      (node (ref "P16") (pin "4") (pinfunction "4_4") (pintype "passive"))
    )
    (net (code "64") (name "/USART1_RX") (class "Default")
      (node (ref "MCU") (pin "69") (pinfunction "PA10/USART1_RX/OTG_FS_ID/DCMI_D1_69") (pintype "bidirectional"))
      (node (ref "P11") (pin "3") (pinfunction "3_3") (pintype "passive"))
    )
    (net (code "65") (name "/USART1_TX") (class "Default")
      (node (ref "MCU") (pin "68") (pinfunction "PA9/USART1_TX/I2C3_SMBA/DCMI_D0/OTG_FS_VBUS_68") (pintype "bidirectional"))
      (node (ref "P11") (pin "4") (pinfunction "4_4") (pintype "passive"))
    )
    (net (code "66") (name "/USART2_RX") (class "Default")
      (node (ref "MCU") (pin "26") (pinfunction "PA3/USART2_RX/OTG_HS_ULPI_D0/ADC123_IN3_26") (pintype "bidirectional"))
      (node (ref "P12") (pin "3") (pinfunction "3_3") (pintype "passive"))
    )
    (net (code "67") (name "/USART2_TX") (class "Default")
      (node (ref "MCU") (pin "25") (pinfunction "PA2/USART2_TX/ADC123_IN2/ETH_MDIO_25") (pintype "bidirectional"))
      (node (ref "P12") (pin "4") (pinfunction "4_4") (pintype "passive"))
    )
    (net (code "68") (name "/USART3_RX") (class "Default")
      (node (ref "MCU") (pin "48") (pinfunction "PB11/I2C2_SDA/USART3_RX/ETH_TX_EN_48") (pintype "bidirectional"))
      (node (ref "Q2") (pin "1") (pinfunction "C_1") (pintype "passive"))
      (node (ref "R29") (pin "1") (pinfunction "1_1") (pintype "passive"))
      (node (ref "R_S3") (pin "2") (pinfunction "2_2") (pintype "passive"))
    )
    (net (code "69") (name "/USART3_TX") (class "Default")
      (node (ref "MCU") (pin "47") (pinfunction "PB10/SPI2_SCK/I2S2_SCL/USART3_TX/OTG_HS_ULPI_D3/OTG_HS_SCL_47") (pintype "bidirectional"))
      (node (ref "P14") (pin "4") (pinfunction "4_4") (pintype "passive"))
    )
    (net (code "70") (name "/VDDA") (class "Default")
      (node (ref "C28") (pin "2") (pinfunction "2_2") (pintype "passive"))
      (node (ref "L0") (pin "1") (pinfunction "1_1") (pintype "passive"))
      (node (ref "L3") (pin "2") (pinfunction "2_2") (pintype "passive"))
      (node (ref "MCU") (pin "22") (pinfunction "VDDA_22") (pintype "power_in"))
    )
    (net (code "71") (name "/VSSA") (class "Default")
      (node (ref "C28") (pin "1") (pinfunction "1_1") (pintype "passive"))
      (node (ref "L4") (pin "2") (pinfunction "2_2") (pintype "passive"))
      (node (ref "MCU") (pin "20") (pinfunction "VSSA_20") (pintype "power_in"))
    )
    (net (code "72") (name "GND") (class "Default")
      (node (ref "C15") (pin "2") (pinfunction "2_2") (pintype "passive"))
      (node (ref "C16") (pin "1") (pinfunction "1_1") (pintype "passive"))
      (node (ref "C21") (pin "2") (pinfunction "2_2") (pintype "passive"))
      (node (ref "C22") (pin "2") (pinfunction "2_2") (pintype "passive"))
      (node (ref "C23") (pin "2") (pinfunction "2_2") (pintype "passive"))
      (node (ref "C24") (pin "2") (pinfunction "2_2") (pintype "passive"))
      (node (ref "C26") (pin "2") (pinfunction "2_2") (pintype "passive"))
      (node (ref "C27") (pin "1") (pinfunction "1_1") (pintype "passive"))
      (node (ref "C32") (pin "1") (pinfunction "1_1") (pintype "passive"))
      (node (ref "C33") (pin "2") (pinfunction "2_2") (pintype "passive"))
      (node (ref "C34") (pin "2") (pinfunction "2_2") (pintype "passive"))
      (node (ref "C35") (pin "2") (pinfunction "2_2") (pintype "passive"))
      (node (ref "C36") (pin "2") (pinfunction "2_2") (pintype "passive"))
      (node (ref "C37") (pin "2") (pinfunction "2_2") (pintype "passive"))
      (node (ref "C40") (pin "2") (pinfunction "2_2") (pintype "passive"))
      (node (ref "C41") (pin "2") (pinfunction "2_2") (pintype "passive"))
      (node (ref "CV1") (pin "2") (pinfunction "2_2") (pintype "passive"))
      (node (ref "CV2") (pin "2") (pinfunction "2_2") (pintype "passive"))
      (node (ref "D5") (pin "1") (pinfunction "A_1") (pintype "passive"))
      (node (ref "D6") (pin "1") (pinfunction "A_1") (pintype "passive"))
      (node (ref "D7") (pin "1") (pinfunction "A_1") (pintype "passive"))
      (node (ref "K4") (pin "1") (pinfunction "1_1") (pintype "passive"))
      (node (ref "K5") (pin "1") (pinfunction "1_1") (pintype "passive"))
      (node (ref "KE") (pin "1") (pinfunction "1_1") (pintype "passive"))
      (node (ref "L4") (pin "1") (pinfunction "1_1") (pintype "passive"))
      (node (ref "LED7") (pin "2") (pinfunction "K_2") (pintype "passive"))
      (node (ref "MCU") (pin "10") (pinfunction "VSS_5_10") (pintype "power_in"))
      (node (ref "MCU") (pin "27") (pinfunction "VSS_4_27") (pintype "power_in"))
      (node (ref "MCU") (pin "74") (pinfunction "VSS_2_74") (pintype "power_in"))
      (node (ref "MCU") (pin "99") (pinfunction "VSS_3_99") (pintype "power_in"))
      (node (ref "P1") (pin "3") (pinfunction "3_3") (pintype "passive"))
      (node (ref "P1") (pin "6") (pinfunction "6_6") (pintype "passive"))
      (node (ref "P10") (pin "2") (pinfunction "2_2") (pintype "passive"))
      (node (ref "P11") (pin "2") (pinfunction "2_2") (pintype "passive"))
      (node (ref "P12") (pin "2") (pinfunction "2_2") (pintype "passive"))
      (node (ref "P14") (pin "2") (pinfunction "2_2") (pintype "passive"))
      (node (ref "P15") (pin "2") (pinfunction "2_2") (pintype "passive"))
      (node (ref "P16") (pin "2") (pinfunction "2_2") (pintype "passive"))
      (node (ref "P18") (pin "2") (pinfunction "2_2") (pintype "passive"))
      (node (ref "P19") (pin "2") (pinfunction "2_2") (pintype "passive"))
      (node (ref "P20") (pin "2") (pinfunction "2_2") (pintype "passive"))
      (node (ref "P21") (pin "2") (pinfunction "2_2") (pintype "passive"))
      (node (ref "P23") (pin "3") (pinfunction "3_3") (pintype "passive"))
      (node (ref "P23") (pin "4") (pinfunction "4_4") (pintype "passive"))
      (node (ref "P30") (pin "5") (pinfunction "5_5") (pintype "passive"))
      (node (ref "P30") (pin "6") (pinfunction "6_6") (pintype "passive"))
      (node (ref "Q0") (pin "3") (pinfunction "E_3") (pintype "passive"))
      (node (ref "Q2") (pin "3") (pinfunction "E_3") (pintype "passive"))
      (node (ref "R20") (pin "1") (pinfunction "1_1") (pintype "passive"))
      (node (ref "R21") (pin "1") (pinfunction "1_1") (pintype "passive"))
      (node (ref "R24") (pin "1") (pinfunction "1_1") (pintype "passive"))
      (node (ref "R_S5") (pin "1") (pinfunction "1_1") (pintype "passive"))
      (node (ref "U4") (pin "1") (pinfunction "GND_1") (pintype "passive"))
      (node (ref "U5") (pin "2") (pinfunction "GND_2") (pintype "passive"))
      (node (ref "U5") (pin "8") (pinfunction "RS_8") (pintype "passive"))
      (node (ref "USB") (pin "5") (pinfunction "GND_5") (pintype "passive"))
      (node (ref "Y3") (pin "3") (pinfunction "OSC3_3") (pintype "passive"))
    )
    (net (code "73") (name "Net-(BEEP-G)") (class "Default")
      (node (ref "BEEP") (pin "2") (pinfunction "G_2") (pintype "passive"))
      (node (ref "Q0") (pin "1") (pinfunction "C_1") (pintype "passive"))
    )
    (net (code "74") (name "Net-(C15-Pad1)") (class "Default")
      (node (ref "C15") (pin "1") (pinfunction "1_1") (pintype "passive"))
      (node (ref "C16") (pin "2") (pinfunction "2_2") (pintype "passive"))
      (node (ref "F4") (pin "1") (pinfunction "1_1") (pintype "passive"))
      (node (ref "U4") (pin "2") (pinfunction "OUT_2") (pintype "passive"))
      (node (ref "U4") (pin "4") (pinfunction "OUT_4") (pintype "passive"))
    )
    (net (code "75") (name "Net-(F6-Pad1)") (class "Default")
      (node (ref "F6") (pin "1") (pinfunction "1_1") (pintype "passive"))
      (node (ref "P11") (pin "1") (pinfunction "1_1") (pintype "passive"))
    )
    (net (code "76") (name "Net-(F7-Pad1)") (class "Default")
      (node (ref "F7") (pin "1") (pinfunction "1_1") (pintype "passive"))
      (node (ref "P12") (pin "1") (pinfunction "1_1") (pintype "passive"))
    )
    (net (code "77") (name "Net-(F8-Pad1)") (class "Default")
      (node (ref "F8") (pin "1") (pinfunction "1_1") (pintype "passive"))
      (node (ref "P14") (pin "1") (pinfunction "1_1") (pintype "passive"))
    )
    (net (code "78") (name "Net-(F9-Pad1)") (class "Default")
      (node (ref "F9") (pin "1") (pinfunction "1_1") (pintype "passive"))
      (node (ref "P15") (pin "1") (pinfunction "1_1") (pintype "passive"))
    )
    (net (code "79") (name "Net-(F10-Pad1)") (class "Default")
      (node (ref "F10") (pin "1") (pinfunction "1_1") (pintype "passive"))
      (node (ref "P16") (pin "1") (pinfunction "1_1") (pintype "passive"))
    )
    (net (code "80") (name "Net-(F11-Pad1)") (class "Default")
      (node (ref "F11") (pin "1") (pinfunction "1_1") (pintype "passive"))
      (node (ref "P30") (pin "2") (pinfunction "2_2") (pintype "passive"))
      (node (ref "P30") (pin "3") (pinfunction "3_3") (pintype "passive"))
      (node (ref "P30") (pin "4") (pinfunction "4_4") (pintype "passive"))
    )
    (net (code "81") (name "Net-(LED4-A)") (class "Default")
      (node (ref "LED4") (pin "1") (pinfunction "A_1") (pintype "passive"))
      (node (ref "R18") (pin "2") (pinfunction "2_2") (pintype "passive"))
    )
    (net (code "82") (name "Net-(LED5-A)") (class "Default")
      (node (ref "LED5") (pin "1") (pinfunction "A_1") (pintype "passive"))
      (node (ref "R19") (pin "2") (pinfunction "2_2") (pintype "passive"))
    )
    (net (code "83") (name "Net-(LED7-A)") (class "Default")
      (node (ref "LED7") (pin "1") (pinfunction "A_1") (pintype "passive"))
      (node (ref "R27") (pin "2") (pinfunction "2_2") (pintype "passive"))
    )
    (net (code "84") (name "Net-(MCU-BOOT0{slash}VPP)") (class "Default")
      (node (ref "MCU") (pin "94") (pinfunction "BOOT0/VPP_94") (pintype "input"))
      (node (ref "R17") (pin "2") (pinfunction "2_2") (pintype "passive"))
    )
    (net (code "85") (name "Net-(MCU-PA4{slash}DCMI_HSYNC{slash}OTG_HS_SOF{slash}I2S3_WS{slash}ADC12_IN4{slash}DAC1_OUT)") (class "Default")
      (node (ref "MCU") (pin "29") (pinfunction "PA4/DCMI_HSYNC/OTG_HS_SOF/I2S3_WS/ADC12_IN4/DAC1_OUT_29") (pintype "bidirectional"))
      (node (ref "T1") (pin "1") (pinfunction "T_1") (pintype "power_in"))
    )
    (net (code "86") (name "Net-(MCU-PA8{slash}MCO1{slash}I2C3_SCL{slash}OTG_FS_SOF)") (class "Default")
      (node (ref "MCU") (pin "67") (pinfunction "PA8/MCO1/I2C3_SCL/OTG_FS_SOF_67") (pintype "bidirectional"))
      (node (ref "T2") (pin "1") (pinfunction "T_1") (pintype "power_in"))
    )
    (net (code "87") (name "Net-(MCU-PB2{slash}BOOT1)") (class "Default")
      (node (ref "MCU") (pin "37") (pinfunction "PB2/BOOT1_37") (pintype "bidirectional"))
      (node (ref "R20") (pin "2") (pinfunction "2_2") (pintype "passive"))
    )
    (net (code "88") (name "Net-(MCU-VCAP1)") (class "Default")
      (node (ref "CV1") (pin "1") (pinfunction "1_1") (pintype "passive"))
      (node (ref "MCU") (pin "49") (pinfunction "VCAP1_49") (pintype "power_in"))
    )
    (net (code "89") (name "Net-(MCU-VCAP2)") (class "Default")
      (node (ref "CV2") (pin "1") (pinfunction "1_1") (pintype "passive"))
      (node (ref "MCU") (pin "73") (pinfunction "VCAP2_73") (pintype "passive"))
    )
    (net (code "90") (name "Net-(MCU-VREF+)") (class "Default")
      (node (ref "L0") (pin "2") (pinfunction "2_2") (pintype "passive"))
      (node (ref "MCU") (pin "21") (pinfunction "VREF+_21") (pintype "power_in"))
    )
    (net (code "91") (name "Net-(P14-Pad3)") (class "Default")
      (node (ref "P14") (pin "3") (pinfunction "3_3") (pintype "passive"))
      (node (ref "R28") (pin "1") (pinfunction "1_1") (pintype "passive"))
      (node (ref "R_S3") (pin "1") (pinfunction "1_1") (pintype "passive"))
    )
    (net (code "92") (name "Net-(Q0-B)") (class "Default")
      (node (ref "Q0") (pin "2") (pinfunction "B_2") (pintype "passive"))
      (node (ref "R21") (pin "2") (pinfunction "2_2") (pintype "passive"))
      (node (ref "R22") (pin "2") (pinfunction "2_2") (pintype "passive"))
    )
    (net (code "93") (name "Net-(Q2-B)") (class "Default")
      (node (ref "Q2") (pin "2") (pinfunction "B_2") (pintype "passive"))
      (node (ref "R28") (pin "2") (pinfunction "2_2") (pintype "passive"))
    )
    (net (code "94") (name "Net-(R17-Pad1)") (class "Default")
      (node (ref "R17") (pin "1") (pinfunction "1_1") (pintype "passive"))
      (node (ref "R_S5") (pin "2") (pinfunction "2_2") (pintype "passive"))
      (node (ref "R_S6") (pin "2") (pinfunction "2_2") (pintype "passive"))
    )
    (net (code "95") (name "Net-(R22-Pad1)") (class "Default")
      (node (ref "R22") (pin "1") (pinfunction "1_1") (pintype "passive"))
      (node (ref "R_S4") (pin "1") (pinfunction "1_1") (pintype "passive"))
    )
    (net (code "96") (name "Net-(U5-CANH)") (class "Default")
      (node (ref "P23") (pin "5") (pinfunction "5_5") (pintype "passive"))
      (node (ref "R25") (pin "2") (pinfunction "2_2") (pintype "passive"))
      (node (ref "U5") (pin "7") (pinfunction "CANH_7") (pintype "passive"))
    )
    (net (code "97") (name "Net-(U5-CANL)") (class "Default")
      (node (ref "P23") (pin "6") (pinfunction "6_6") (pintype "passive"))
      (node (ref "R25") (pin "1") (pinfunction "1_1") (pintype "passive"))
      (node (ref "U5") (pin "6") (pinfunction "CANL_6") (pintype "passive"))
    )
    (net (code "98") (name "Net-(USB-D+)") (class "Default")
      (node (ref "R26") (pin "2") (pinfunction "2_2") (pintype "passive"))
      (node (ref "USB") (pin "3") (pinfunction "D+_3") (pintype "passive"))
    )
    (net (code "99") (name "Net-(USB-D-)") (class "Default")
      (node (ref "R2") (pin "2") (pinfunction "2_2") (pintype "passive"))
      (node (ref "USB") (pin "2") (pinfunction "D-_2") (pintype "passive"))
    )
    (net (code "100") (name "Net-(USB-VCC)") (class "Default")
      (node (ref "F18") (pin "1") (pinfunction "1_1") (pintype "passive"))
      (node (ref "USB") (pin "1") (pinfunction "VCC_1") (pintype "passive"))
    )
    (net (code "101") (name "VCC3.3") (class "Default")
      (node (ref "BEEP") (pin "1") (pinfunction "P_1") (pintype "passive"))
      (node (ref "C21") (pin "1") (pinfunction "1_1") (pintype "passive"))
      (node (ref "C22") (pin "1") (pinfunction "1_1") (pintype "passive"))
      (node (ref "C23") (pin "1") (pinfunction "1_1") (pintype "passive"))
      (node (ref "C24") (pin "1") (pinfunction "1_1") (pintype "passive"))
      (node (ref "C26") (pin "1") (pinfunction "1_1") (pintype "passive"))
      (node (ref "C27") (pin "2") (pinfunction "2_2") (pintype "passive"))
      (node (ref "D5") (pin "2") (pinfunction "K_2") (pintype "passive"))
      (node (ref "D6") (pin "2") (pinfunction "K_2") (pintype "passive"))
      (node (ref "F4") (pin "2") (pinfunction "2_2") (pintype "passive"))
      (node (ref "L3") (pin "1") (pinfunction "1_1") (pintype "passive"))
      (node (ref "MCU") (pin "100") (pinfunction "VDD_3_100") (pintype "power_in"))
      (node (ref "MCU") (pin "11") (pinfunction "VDD_5_11") (pintype "power_in"))
      (node (ref "MCU") (pin "19") (pinfunction "VDD_12_19") (pintype "power_in"))
      (node (ref "MCU") (pin "28") (pinfunction "VDD_4_28") (pintype "power_in"))
      (node (ref "MCU") (pin "50") (pinfunction "VDD_1_50") (pintype "power_in"))
      (node (ref "MCU") (pin "6") (pinfunction "VBAT_6") (pintype "power_in"))
      (node (ref "MCU") (pin "75") (pinfunction "VDD_2_75") (pintype "power_in"))
      (node (ref "P1") (pin "2") (pinfunction "2_2") (pintype "passive"))
      (node (ref "P1") (pin "5") (pinfunction "5_5") (pintype "passive"))
      (node (ref "P10") (pin "1") (pinfunction "1_1") (pintype "passive"))
      (node (ref "P18") (pin "1") (pinfunction "1_1") (pintype "passive"))
      (node (ref "P19") (pin "1") (pinfunction "1_1") (pintype "passive"))
      (node (ref "P20") (pin "1") (pinfunction "1_1") (pintype "passive"))
      (node (ref "P21") (pin "1") (pinfunction "1_1") (pintype "passive"))
      (node (ref "R16") (pin "1") (pinfunction "1_1") (pintype "passive"))
      (node (ref "R18") (pin "1") (pinfunction "1_1") (pintype "passive"))
      (node (ref "R19") (pin "1") (pinfunction "1_1") (pintype "passive"))
      (node (ref "R27") (pin "1") (pinfunction "1_1") (pintype "passive"))
      (node (ref "R29") (pin "2") (pinfunction "2_2") (pintype "passive"))
      (node (ref "R_S6") (pin "1") (pinfunction "1_1") (pintype "passive"))
      (node (ref "U5") (pin "3") (pinfunction "VCC_3") (pintype "passive"))
    )
    (net (code "102") (name "VCC5") (class "Default")
      (node (ref "C33") (pin "1") (pinfunction "1_1") (pintype "passive"))
      (node (ref "C34") (pin "1") (pinfunction "1_1") (pintype "passive"))
      (node (ref "C35") (pin "1") (pinfunction "1_1") (pintype "passive"))
      (node (ref "C36") (pin "1") (pinfunction "1_1") (pintype "passive"))
      (node (ref "C37") (pin "1") (pinfunction "1_1") (pintype "passive"))
      (node (ref "D7") (pin "2") (pinfunction "K_2") (pintype "passive"))
      (node (ref "F10") (pin "2") (pinfunction "2_2") (pintype "passive"))
      (node (ref "F11") (pin "2") (pinfunction "2_2") (pintype "passive"))
      (node (ref "F18") (pin "2") (pinfunction "2_2") (pintype "passive"))
      (node (ref "F6") (pin "2") (pinfunction "2_2") (pintype "passive"))
      (node (ref "F7") (pin "2") (pinfunction "2_2") (pintype "passive"))
      (node (ref "F8") (pin "2") (pinfunction "2_2") (pintype "passive"))
      (node (ref "F9") (pin "2") (pinfunction "2_2") (pintype "passive"))
      (node (ref "P1") (pin "1") (pinfunction "1_1") (pintype "passive"))
      (node (ref "P1") (pin "4") (pinfunction "4_4") (pintype "passive"))
      (node (ref "P23") (pin "1") (pinfunction "1_1") (pintype "passive"))
      (node (ref "P23") (pin "2") (pinfunction "2_2") (pintype "passive"))
      (node (ref "U4") (pin "3") (pinfunction "IN_3") (pintype "passive"))
    )
    (net (code "103") (name "VCC12") (class "Default")
      (node (ref "P30") (pin "1") (pinfunction "1_1") (pintype "passive"))
      (node (ref "R23") (pin "1") (pinfunction "1_1") (pintype "passive"))
    )
    (net (code "104") (name "unconnected-(MCU-FSMC_D4{slash}PE7-Pad38)") (class "Default")
      (node (ref "MCU") (pin "38") (pinfunction "FSMC_D4/PE7_38") (pintype "bidirectional+no_connect"))
    )
    (net (code "105") (name "unconnected-(MCU-FSMC_D5{slash}PE8-Pad39)") (class "Default")
      (node (ref "MCU") (pin "39") (pinfunction "FSMC_D5/PE8_39") (pintype "bidirectional+no_connect"))
    )
    (net (code "106") (name "unconnected-(MCU-FSMC_D7{slash}PE10-Pad41)") (class "Default")
      (node (ref "MCU") (pin "41") (pinfunction "FSMC_D7/PE10_41") (pintype "bidirectional"))
    )
    (net (code "107") (name "unconnected-(MCU-FSMC_D9{slash}PE12-Pad43)") (class "Default")
      (node (ref "MCU") (pin "43") (pinfunction "FSMC_D9/PE12_43") (pintype "bidirectional+no_connect"))
    )
    (net (code "108") (name "unconnected-(MCU-FSMC_NE1{slash}FSMC_NCE2{slash}PD7-Pad88)") (class "Default")
      (node (ref "MCU") (pin "88") (pinfunction "FSMC_NE1/FSMC_NCE2/PD7_88") (pintype "bidirectional+no_connect"))
    )
    (net (code "109") (name "unconnected-(MCU-PA15{slash}JTDI{slash}I2S3_WS-Pad77)") (class "Default")
      (node (ref "MCU") (pin "77") (pinfunction "PA15/JTDI/I2S3_WS_77") (pintype "bidirectional+no_connect"))
    )
    (net (code "110") (name "unconnected-(MCU-PB3{slash}JTDO{slash}SPI3_SCK{slash}I2S3_CK{slash}SPI1_SCK-Pad89)") (class "Default")
      (node (ref "MCU") (pin "89") (pinfunction "PB3/JTDO/SPI3_SCK/I2S3_CK/SPI1_SCK_89") (pintype "bidirectional+no_connect"))
    )
    (net (code "111") (name "unconnected-(MCU-PB7{slash}I2C1_SDA{slash}FSMC_NL{slash}DCMI_VSYNC{slash}USART1_RX-Pad93)") (class "Default")
      (node (ref "MCU") (pin "93") (pinfunction "PB7/I2C1_SDA/FSMC_NL/DCMI_VSYNC/USART1_RX_93") (pintype "bidirectional+no_connect"))
    )
    (net (code "112") (name "unconnected-(MCU-SPI3_SCK{slash}I2S3_CK{slash}UART4_TX{slash}SDIO_D2{slash}USART3_TX{slash}PC10-Pad78)") (class "Default")
      (node (ref "MCU") (pin "78") (pinfunction "SPI3_SCK/I2S3_CK/UART4_TX/SDIO_D2/USART3_TX/PC10_78") (pintype "bidirectional+no_connect"))
    )
    (net (code "113") (name "unconnected-(MCU-TAMPER-RTC_AF1{slash}PC13-Pad7)") (class "Default")
      (node (ref "MCU") (pin "7") (pinfunction "TAMPER-RTC_AF1/PC13_7") (pintype "bidirectional+no_connect"))
    )
    (net (code "114") (name "unconnected-(MCU-UART4_RX{slash}SPI3_MISO{slash}SDIO_D3{slash}DCMI_D4{slash}USART3_RX{slash}I2S3ext_SD{slash}PC11-Pad79)") (class "Default")
      (node (ref "MCU") (pin "79") (pinfunction "UART4_RX/SPI3_MISO/SDIO_D3/DCMI_D4/USART3_RX/I2S3ext_SD/PC11_79") (pintype "bidirectional+no_connect"))
    )
    (net (code "115") (name "unconnected-(U5-SHDN-Pad5)") (class "Default")
      (node (ref "U5") (pin "5") (pinfunction "SHDN_5") (pintype "passive+no_connect"))
    )
    (net (code "116") (name "unconnected-(USB-NC-Pad4)") (class "Default")
      (node (ref "USB") (pin "4") (pinfunction "NC_4") (pintype "passive+no_connect"))
    )
  )
)
